# 23005_3.net
KiCad netlist of a schematic drawn in Altium Designer
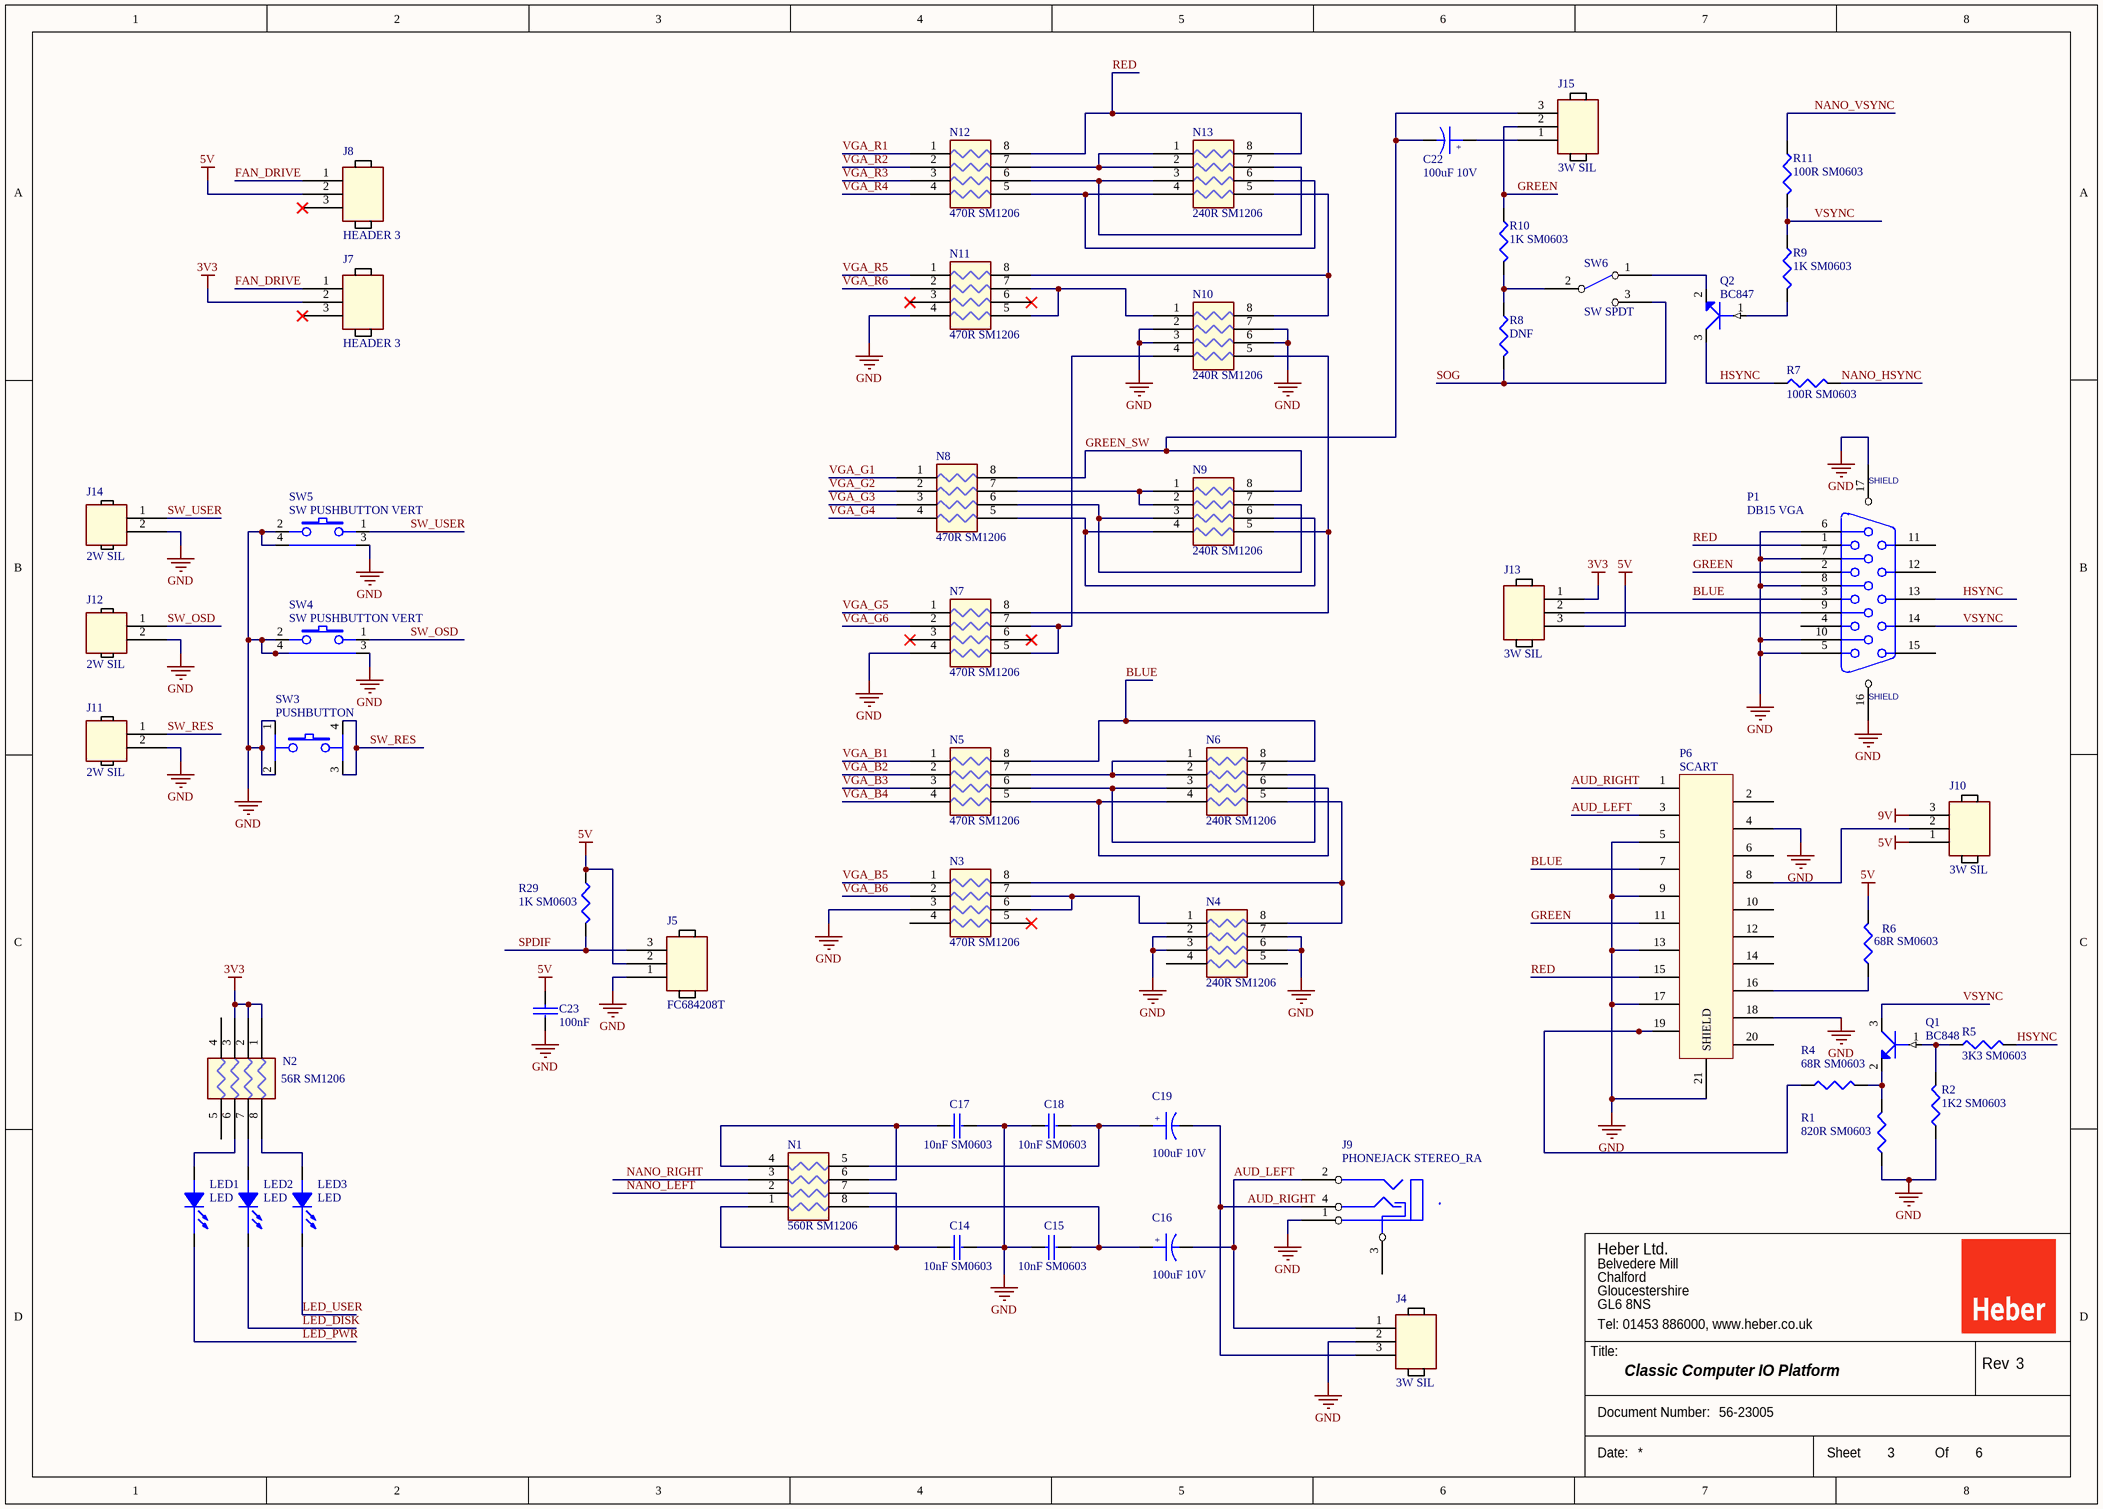
[diagram p0: 23005_3.SchDoc]

(export (version "E")
  (design (tool "Eeschema 10.0.6"))
  (components
    (comp (ref "C14")
      (value "10nF SM0603")
      (footprint "SM0603")
      (libsource (lib "LIBRARY1_Library") (part "C"))
    )
    (comp (ref "C15")
      (value "10nF SM0603")
      (footprint "SM0603")
      (libsource (lib "LIBRARY1_Library") (part "C"))
    )
    (comp (ref "C16")
      (value "100uF 10V")
      (footprint "SM1206")
      (libsource (lib "LIBRARY1_Library") (part "CAP_POL"))
    )
    (comp (ref "C17")
      (value "10nF SM0603")
      (footprint "SM0603")
      (libsource (lib "LIBRARY1_Library") (part "C"))
    )
    (comp (ref "C18")
      (value "10nF SM0603")
      (footprint "SM0603")
      (libsource (lib "LIBRARY1_Library") (part "C"))
    )
    (comp (ref "C19")
      (value "100uF 10V")
      (footprint "SM1206")
      (libsource (lib "LIBRARY1_Library") (part "CAP_POL"))
    )
    (comp (ref "C22")
      (value "100uF 10V")
      (footprint "SM1206")
      (libsource (lib "LIBRARY1_Library") (part "CAP_POL"))
    )
    (comp (ref "C23") (value "100nF") (footprint "SM0603") (libsource (lib "LIBRARY1_Library") (part "C")))
    (comp (ref "J4") (value "3W SIL") (footprint "3WSIL") (libsource (lib "") (part "HEADER 3_2")))
    (comp (ref "J5")
      (value "FC684208T")
      (footprint "FCR684208T")
      (libsource (lib "LIBRARY1_Library") (part "HEADER 3"))
    )
    (comp (ref "J7") (value "HEADER 3") (footprint "3W0.1KK") (libsource (lib "") (part "HEADER 3_2")))
    (comp (ref "J8") (value "HEADER 3") (footprint "3W0.1KK") (libsource (lib "") (part "HEADER 3_2")))
    (comp (ref "J9")
      (value "PHONEJACK STEREO_RA")
      (footprint "JACKSOCKET-STEREO")
      (libsource (lib "LIBRARY1_Library") (part "PHONEJACK STEREO_RA"))
    )
    (comp (ref "J10")
      (value "3W SIL")
      (footprint "3WSIL")
      (libsource (lib "LIBRARY1_Library") (part "HEADER 3"))
    )
    (comp (ref "J11")
      (value "2W SIL")
      (footprint "2WSIL")
      (libsource (lib "LIBRARY1_Library") (part "HEADER 2"))
    )
    (comp (ref "J12")
      (value "2W SIL")
      (footprint "2WSIL")
      (libsource (lib "LIBRARY1_Library") (part "HEADER 2"))
    )
    (comp (ref "J13") (value "3W SIL") (footprint "3WSIL") (libsource (lib "") (part "HEADER 3_1")))
    (comp (ref "J14")
      (value "2W SIL")
      (footprint "2WSIL")
      (libsource (lib "LIBRARY1_Library") (part "HEADER 2"))
    )
    (comp (ref "J15")
      (value "3W SIL")
      (footprint "3WSIL")
      (libsource (lib "LIBRARY1_Library") (part "HEADER 3"))
    )
    (comp (ref "LED1")
      (value "LED")
      (footprint "SM0603LED_1")
      (libsource (lib "LIBRARY1_Library") (part "LED"))
    )
    (comp (ref "LED2")
      (value "LED")
      (footprint "SM0603LED_1")
      (libsource (lib "LIBRARY1_Library") (part "LED"))
    )
    (comp (ref "LED3")
      (value "LED")
      (footprint "SM0603LED_1")
      (libsource (lib "LIBRARY1_Library") (part "LED"))
    )
    (comp (ref "N1")
      (value "560R SM1206")
      (footprint "1206RES4_I2")
      (libsource (lib "LIBRARY1_Library") (part "RESISTOR DIP 4"))
    )
    (comp (ref "N2")
      (value "56R SM1206")
      (footprint "1206RES4_I2")
      (libsource (lib "") (part "RESISTOR DIP 4_2"))
    )
    (comp (ref "N3")
      (value "470R SM1206")
      (footprint "1206RES4_I2")
      (libsource (lib "") (part "RESISTOR DIP 4_1"))
    )
    (comp (ref "N4")
      (value "240R SM1206")
      (footprint "1206RES4_I2")
      (libsource (lib "") (part "RESISTOR DIP 4_1"))
    )
    (comp (ref "N5")
      (value "470R SM1206")
      (footprint "1206RES4_I2")
      (libsource (lib "") (part "RESISTOR DIP 4_1"))
    )
    (comp (ref "N6")
      (value "240R SM1206")
      (footprint "1206RES4_I2")
      (libsource (lib "") (part "RESISTOR DIP 4_1"))
    )
    (comp (ref "N7")
      (value "470R SM1206")
      (footprint "1206RES4_I2")
      (libsource (lib "") (part "RESISTOR DIP 4_1"))
    )
    (comp (ref "N8")
      (value "470R SM1206")
      (footprint "1206RES4_I2")
      (libsource (lib "") (part "RESISTOR DIP 4_1"))
    )
    (comp (ref "N9")
      (value "240R SM1206")
      (footprint "1206RES4_I2")
      (libsource (lib "") (part "RESISTOR DIP 4_1"))
    )
    (comp (ref "N10")
      (value "240R SM1206")
      (footprint "1206RES4_I2")
      (libsource (lib "") (part "RESISTOR DIP 4_1"))
    )
    (comp (ref "N11")
      (value "470R SM1206")
      (footprint "1206RES4_I2")
      (libsource (lib "") (part "RESISTOR DIP 4_1"))
    )
    (comp (ref "N12")
      (value "470R SM1206")
      (footprint "1206RES4_I2")
      (libsource (lib "") (part "RESISTOR DIP 4_1"))
    )
    (comp (ref "N13")
      (value "240R SM1206")
      (footprint "1206RES4_I2")
      (libsource (lib "") (part "RESISTOR DIP 4_1"))
    )
    (comp (ref "P1")
      (value "DB15 VGA")
      (footprint "15WVGASKTRA")
      (libsource (lib "LIBRARY1_Library") (part "CONNECTOR DB15 VGA SHIELDED"))
    )
    (comp (ref "P6")
      (value "SCART")
      (footprint "K-SCART-024")
      (libsource (lib "LIBRARY1_Library") (part "SCART"))
    )
    (comp (ref "Q1")
      (value "BC848")
      (footprint "SOT23")
      (libsource (lib "LIBRARY1_Library") (part "BC846AL_1"))
    )
    (comp (ref "Q2")
      (value "BC847")
      (footprint "SOT23")
      (libsource (lib "LIBRARY1_Library") (part "BC846AL_1"))
    )
    (comp (ref "R1")
      (value "820R SM0603")
      (footprint "SM0603")
      (libsource (lib "LIBRARY1_Library") (part "RES"))
    )
    (comp (ref "R2")
      (value "1K2 SM0603")
      (footprint "SM0603")
      (libsource (lib "LIBRARY1_Library") (part "RES"))
    )
    (comp (ref "R4")
      (value "68R SM0603")
      (footprint "SM0603")
      (libsource (lib "LIBRARY1_Library") (part "RES"))
    )
    (comp (ref "R5")
      (value "3K3 SM0603")
      (footprint "SM0603")
      (libsource (lib "LIBRARY1_Library") (part "RES"))
    )
    (comp (ref "R6")
      (value "68R SM0603")
      (footprint "SM0603")
      (libsource (lib "LIBRARY1_Library") (part "RES"))
    )
    (comp (ref "R7")
      (value "100R SM0603")
      (footprint "SM0603")
      (libsource (lib "LIBRARY1_Library") (part "RES"))
    )
    (comp (ref "R8") (value "DNF") (footprint "SM0603") (libsource (lib "LIBRARY1_Library") (part "RES")))
    (comp (ref "R9")
      (value "1K SM0603")
      (footprint "SM0603")
      (libsource (lib "LIBRARY1_Library") (part "RES"))
    )
    (comp (ref "R10")
      (value "1K SM0603")
      (footprint "SM0603")
      (libsource (lib "LIBRARY1_Library") (part "RES"))
    )
    (comp (ref "R11")
      (value "100R SM0603")
      (footprint "SM0603")
      (libsource (lib "LIBRARY1_Library") (part "RES"))
    )
    (comp (ref "R29")
      (value "1K SM0603")
      (footprint "SM0603")
      (libsource (lib "LIBRARY1_Library") (part "RES"))
    )
    (comp (ref "SW3")
      (value "PUSHBUTTON")
      (footprint "SW_SM_6MM")
      (libsource (lib "LIBRARY1_Library") (part "SW PUSHBUTTON"))
    )
    (comp (ref "SW4")
      (value "SW PUSHBUTTON VERT")
      (footprint "SW_TS6H2A")
      (libsource (lib "LIBRARY1_Library") (part "SW PUSHBUTTON VERT"))
    )
    (comp (ref "SW5")
      (value "SW PUSHBUTTON VERT")
      (footprint "SW_TS6H2A")
      (libsource (lib "LIBRARY1_Library") (part "SW PUSHBUTTON VERT"))
    )
    (comp (ref "SW6")
      (value "SW SPDT")
      (footprint "SW_ITT_OS102011MS2QN1")
      (libsource (lib "LIBRARY1_Library") (part "SW SPDT"))
    )
  )
  (nets
    (net (code "1") (name "/AUD_LEFT") (class "Default")
      (node (ref "C16") (pin "2") (pinfunction "2_2") (pintype "passive"))
      (node (ref "J4") (pin "1") (pinfunction "1_1") (pintype "passive"))
      (node (ref "J9") (pin "2") (pinfunction "2_2") (pintype "passive"))
      (node (ref "P6") (pin "3") (pinfunction "108_3") (pintype "passive"))
    )
    (net (code "2") (name "/AUD_RIGHT") (class "Default")
      (node (ref "C19") (pin "2") (pinfunction "2_2") (pintype "passive"))
      (node (ref "J4") (pin "3") (pinfunction "3_3") (pintype "passive"))
      (node (ref "J9") (pin "4") (pinfunction "4_4") (pintype "passive"))
      (node (ref "P6") (pin "1") (pinfunction "106_1") (pintype "passive"))
    )
    (net (code "3") (name "/BLUE") (class "Default")
      (node (ref "N5") (pin "8") (pinfunction "8_8") (pintype "passive"))
      (node (ref "N6") (pin "8") (pinfunction "8_8") (pintype "passive"))
      (node (ref "P1") (pin "3") (pinfunction "3_3") (pintype "passive"))
      (node (ref "P6") (pin "7") (pinfunction "112_7") (pintype "passive"))
    )
    (net (code "4") (name "/FAN_DRIVE") (class "Default")
      (node (ref "J7") (pin "1") (pinfunction "1_1") (pintype "passive"))
      (node (ref "J8") (pin "1") (pinfunction "1_1") (pintype "passive"))
    )
    (net (code "5") (name "/GREEN") (class "Default")
      (node (ref "J15") (pin "2") (pinfunction "2_2") (pintype "passive"))
      (node (ref "P1") (pin "2") (pinfunction "2_2") (pintype "passive"))
      (node (ref "P6") (pin "11") (pinfunction "112_11") (pintype "passive"))
      (node (ref "R10") (pin "1") (pinfunction "1_1") (pintype "passive"))
    )
    (net (code "6") (name "/GREEN_SW") (class "Default")
      (node (ref "C22") (pin "2") (pinfunction "2_2") (pintype "passive"))
      (node (ref "J15") (pin "3") (pinfunction "3_3") (pintype "passive"))
      (node (ref "N8") (pin "8") (pinfunction "8_8") (pintype "passive"))
      (node (ref "N9") (pin "8") (pinfunction "8_8") (pintype "passive"))
    )
    (net (code "7") (name "/HSYNC") (class "Default")
      (node (ref "P1") (pin "13") (pinfunction "13_13") (pintype "passive"))
      (node (ref "Q2") (pin "3") (pinfunction "C_3") (pintype "passive"))
      (node (ref "R5") (pin "1") (pinfunction "1_1") (pintype "passive"))
      (node (ref "R7") (pin "1") (pinfunction "1_1") (pintype "passive"))
    )
    (net (code "8") (name "/LED_DISK") (class "Default")
      (node (ref "LED2") (pin "2") (pinfunction "CATHODE_2") (pintype "passive"))
    )
    (net (code "9") (name "/LED_PWR") (class "Default")
      (node (ref "LED1") (pin "2") (pinfunction "CATHODE_2") (pintype "passive"))
    )
    (net (code "10") (name "/LED_USER") (class "Default")
      (node (ref "LED3") (pin "2") (pinfunction "CATHODE_2") (pintype "passive"))
    )
    (net (code "11") (name "/NANO_HSYNC") (class "Default")
      (node (ref "R7") (pin "2") (pinfunction "2_2") (pintype "passive"))
    )
    (net (code "12") (name "/NANO_LEFT") (class "Default")
      (node (ref "N1") (pin "2") (pinfunction "2_2") (pintype "passive"))
    )
    (net (code "13") (name "/NANO_RIGHT") (class "Default")
      (node (ref "N1") (pin "3") (pinfunction "3_3") (pintype "passive"))
    )
    (net (code "14") (name "/NANO_VSYNC") (class "Default")
      (node (ref "R11") (pin "1") (pinfunction "1_1") (pintype "passive"))
    )
    (net (code "15") (name "/RED") (class "Default")
      (node (ref "N12") (pin "8") (pinfunction "8_8") (pintype "passive"))
      (node (ref "N13") (pin "8") (pinfunction "8_8") (pintype "passive"))
      (node (ref "P1") (pin "1") (pinfunction "1_1") (pintype "passive"))
      (node (ref "P6") (pin "15") (pinfunction "112_15") (pintype "passive"))
    )
    (net (code "16") (name "/SOG") (class "Default")
      (node (ref "R8") (pin "2") (pinfunction "2_2") (pintype "passive"))
      (node (ref "SW6") (pin "3") (pinfunction "NO_3") (pintype "passive"))
    )
    (net (code "17") (name "/SPDIF") (class "Default")
      (node (ref "J5") (pin "3") (pinfunction "3_3") (pintype "passive"))
      (node (ref "R29") (pin "2") (pinfunction "2_2") (pintype "passive"))
    )
    (net (code "18") (name "/SW_OSD") (class "Default")
      (node (ref "J12") (pin "1") (pinfunction "1_1") (pintype "passive"))
      (node (ref "SW4") (pin "1") (pinfunction "3_1") (pintype "passive"))
    )
    (net (code "19") (name "/SW_RES") (class "Default")
      (node (ref "J11") (pin "1") (pinfunction "1_1") (pintype "passive"))
      (node (ref "SW3") (pin "3") (pinfunction "2_3") (pintype "passive"))
      (node (ref "SW3") (pin "4") (pinfunction "4_4") (pintype "passive"))
    )
    (net (code "20") (name "/SW_USER") (class "Default")
      (node (ref "J14") (pin "1") (pinfunction "1_1") (pintype "passive"))
      (node (ref "SW5") (pin "1") (pinfunction "3_1") (pintype "passive"))
    )
    (net (code "21") (name "/VGA_B1") (class "Default")
      (node (ref "N5") (pin "1") (pinfunction "1_1") (pintype "passive"))
    )
    (net (code "22") (name "/VGA_B2") (class "Default")
      (node (ref "N5") (pin "2") (pinfunction "2_2") (pintype "passive"))
    )
    (net (code "23") (name "/VGA_B3") (class "Default")
      (node (ref "N5") (pin "3") (pinfunction "3_3") (pintype "passive"))
    )
    (net (code "24") (name "/VGA_B4") (class "Default")
      (node (ref "N5") (pin "4") (pinfunction "4_4") (pintype "passive"))
    )
    (net (code "25") (name "/VGA_B5") (class "Default")
      (node (ref "N3") (pin "1") (pinfunction "1_1") (pintype "passive"))
    )
    (net (code "26") (name "/VGA_B6") (class "Default")
      (node (ref "N3") (pin "2") (pinfunction "2_2") (pintype "passive"))
    )
    (net (code "27") (name "/VGA_G1") (class "Default")
      (node (ref "N8") (pin "1") (pinfunction "1_1") (pintype "passive"))
    )
    (net (code "28") (name "/VGA_G2") (class "Default")
      (node (ref "N8") (pin "2") (pinfunction "2_2") (pintype "passive"))
    )
    (net (code "29") (name "/VGA_G3") (class "Default")
      (node (ref "N8") (pin "3") (pinfunction "3_3") (pintype "passive"))
    )
    (net (code "30") (name "/VGA_G4") (class "Default")
      (node (ref "N8") (pin "4") (pinfunction "4_4") (pintype "passive"))
    )
    (net (code "31") (name "/VGA_G5") (class "Default")
      (node (ref "N7") (pin "1") (pinfunction "1_1") (pintype "passive"))
    )
    (net (code "32") (name "/VGA_G6") (class "Default")
      (node (ref "N7") (pin "2") (pinfunction "2_2") (pintype "passive"))
    )
    (net (code "33") (name "/VGA_R1") (class "Default")
      (node (ref "N12") (pin "1") (pinfunction "1_1") (pintype "passive"))
    )
    (net (code "34") (name "/VGA_R2") (class "Default")
      (node (ref "N12") (pin "2") (pinfunction "2_2") (pintype "passive"))
    )
    (net (code "35") (name "/VGA_R3") (class "Default")
      (node (ref "N12") (pin "3") (pinfunction "3_3") (pintype "passive"))
    )
    (net (code "36") (name "/VGA_R4") (class "Default")
      (node (ref "N12") (pin "4") (pinfunction "4_4") (pintype "passive"))
    )
    (net (code "37") (name "/VGA_R5") (class "Default")
      (node (ref "N11") (pin "1") (pinfunction "1_1") (pintype "passive"))
    )
    (net (code "38") (name "/VGA_R6") (class "Default")
      (node (ref "N11") (pin "2") (pinfunction "2_2") (pintype "passive"))
    )
    (net (code "39") (name "/VSYNC") (class "Default")
      (node (ref "P1") (pin "14") (pinfunction "14_14") (pintype "passive"))
      (node (ref "Q1") (pin "3") (pinfunction "C_3") (pintype "passive"))
      (node (ref "R11") (pin "2") (pinfunction "2_2") (pintype "passive"))
      (node (ref "R9") (pin "1") (pinfunction "1_1") (pintype "passive"))
    )
    (net (code "40") (name "3V3") (class "Default")
      (node (ref "J13") (pin "1") (pinfunction "1_1") (pintype "passive"))
      (node (ref "J7") (pin "2") (pinfunction "2_2") (pintype "passive"))
      (node (ref "N2") (pin "1") (pinfunction "1_1") (pintype "passive"))
      (node (ref "N2") (pin "2") (pinfunction "2_2") (pintype "passive"))
      (node (ref "N2") (pin "3") (pinfunction "3_3") (pintype "passive"))
    )
    (net (code "41") (name "5V") (class "Default")
      (node (ref "C23") (pin "1") (pinfunction "1_1") (pintype "passive"))
      (node (ref "J10") (pin "1") (pinfunction "1_1") (pintype "passive"))
      (node (ref "J13") (pin "3") (pinfunction "3_3") (pintype "passive"))
      (node (ref "J5") (pin "2") (pinfunction "2_2") (pintype "passive"))
      (node (ref "J8") (pin "2") (pinfunction "2_2") (pintype "passive"))
      (node (ref "R29") (pin "1") (pinfunction "1_1") (pintype "passive"))
      (node (ref "R6") (pin "2") (pinfunction "2_2") (pintype "passive"))
    )
    (net (code "42") (name "9V") (class "Default")
      (node (ref "J10") (pin "3") (pinfunction "3_3") (pintype "passive"))
    )
    (net (code "43") (name "GND") (class "Default")
      (node (ref "C14") (pin "2") (pinfunction "2_2") (pintype "passive"))
      (node (ref "C15") (pin "1") (pinfunction "1_1") (pintype "passive"))
      (node (ref "C17") (pin "2") (pinfunction "2_2") (pintype "passive"))
      (node (ref "C18") (pin "1") (pinfunction "1_1") (pintype "passive"))
      (node (ref "C23") (pin "2") (pinfunction "2_2") (pintype "passive"))
      (node (ref "J11") (pin "2") (pinfunction "2_2") (pintype "passive"))
      (node (ref "J12") (pin "2") (pinfunction "2_2") (pintype "passive"))
      (node (ref "J14") (pin "2") (pinfunction "2_2") (pintype "passive"))
      (node (ref "J4") (pin "2") (pinfunction "2_2") (pintype "passive"))
      (node (ref "J5") (pin "1") (pinfunction "1_1") (pintype "passive"))
      (node (ref "J9") (pin "1") (pinfunction "1_1") (pintype "passive"))
      (node (ref "N10") (pin "2") (pinfunction "2_2") (pintype "passive"))
      (node (ref "N10") (pin "3") (pinfunction "3_3") (pintype "passive"))
      (node (ref "N10") (pin "6") (pinfunction "6_6") (pintype "passive"))
      (node (ref "N10") (pin "7") (pinfunction "7_7") (pintype "passive"))
      (node (ref "N11") (pin "4") (pinfunction "4_4") (pintype "passive"))
      (node (ref "N3") (pin "3") (pinfunction "3_3") (pintype "passive"))
      (node (ref "N4") (pin "2") (pinfunction "2_2") (pintype "passive"))
      (node (ref "N4") (pin "3") (pinfunction "3_3") (pintype "passive"))
      (node (ref "N4") (pin "6") (pinfunction "6_6") (pintype "passive"))
      (node (ref "N4") (pin "7") (pinfunction "7_7") (pintype "passive"))
      (node (ref "N7") (pin "4") (pinfunction "4_4") (pintype "passive"))
      (node (ref "P1") (pin "10") (pinfunction "10_10") (pintype "passive"))
      (node (ref "P1") (pin "16") (pinfunction "16_16") (pintype "passive"))
      (node (ref "P1") (pin "17") (pinfunction "17_17") (pintype "passive"))
      (node (ref "P1") (pin "5") (pinfunction "5_5") (pintype "passive"))
      (node (ref "P1") (pin "6") (pinfunction "6_6") (pintype "passive"))
      (node (ref "P1") (pin "7") (pinfunction "7_7") (pintype "passive"))
      (node (ref "P1") (pin "8") (pinfunction "8_8") (pintype "passive"))
      (node (ref "P6") (pin "13") (pinfunction "112_13") (pintype "passive"))
      (node (ref "P6") (pin "17") (pinfunction "112_17") (pintype "passive"))
      (node (ref "P6") (pin "18") (pinfunction "112_18") (pintype "passive"))
      (node (ref "P6") (pin "21") (pinfunction "SHIELD_21") (pintype "passive"))
      (node (ref "P6") (pin "4") (pinfunction "109_4") (pintype "passive"))
      (node (ref "P6") (pin "5") (pinfunction "110_5") (pintype "passive"))
      (node (ref "P6") (pin "9") (pinfunction "112_9") (pintype "passive"))
      (node (ref "R1") (pin "2") (pinfunction "2_2") (pintype "passive"))
      (node (ref "R2") (pin "2") (pinfunction "2_2") (pintype "passive"))
      (node (ref "SW3") (pin "1") (pinfunction "3_1") (pintype "passive"))
      (node (ref "SW3") (pin "2") (pinfunction "1_2") (pintype "passive"))
      (node (ref "SW4") (pin "2") (pinfunction "1_2") (pintype "passive"))
      (node (ref "SW4") (pin "3") (pinfunction "2_3") (pintype "passive"))
      (node (ref "SW4") (pin "4") (pinfunction "4_4") (pintype "passive"))
      (node (ref "SW5") (pin "2") (pinfunction "1_2") (pintype "passive"))
      (node (ref "SW5") (pin "3") (pinfunction "2_3") (pintype "passive"))
      (node (ref "SW5") (pin "4") (pinfunction "4_4") (pintype "passive"))
    )
    (net (code "44") (name "Net-(C14-Pad1)") (class "Default")
      (node (ref "C14") (pin "1") (pinfunction "1_1") (pintype "passive"))
      (node (ref "N1") (pin "1") (pinfunction "1_1") (pintype "passive"))
      (node (ref "N1") (pin "7") (pinfunction "7_7") (pintype "passive"))
    )
    (net (code "45") (name "Net-(C15-Pad2)") (class "Default")
      (node (ref "C15") (pin "2") (pinfunction "2_2") (pintype "passive"))
      (node (ref "C16") (pin "1") (pinfunction "1_1") (pintype "passive"))
      (node (ref "N1") (pin "8") (pinfunction "8_8") (pintype "passive"))
    )
    (net (code "46") (name "Net-(C17-Pad1)") (class "Default")
      (node (ref "C17") (pin "1") (pinfunction "1_1") (pintype "passive"))
      (node (ref "N1") (pin "4") (pinfunction "4_4") (pintype "passive"))
      (node (ref "N1") (pin "6") (pinfunction "6_6") (pintype "passive"))
    )
    (net (code "47") (name "Net-(C18-Pad2)") (class "Default")
      (node (ref "C18") (pin "2") (pinfunction "2_2") (pintype "passive"))
      (node (ref "C19") (pin "1") (pinfunction "1_1") (pintype "passive"))
      (node (ref "N1") (pin "5") (pinfunction "5_5") (pintype "passive"))
    )
    (net (code "48") (name "Net-(C22-Pad1)") (class "Default")
      (node (ref "C22") (pin "1") (pinfunction "1_1") (pintype "passive"))
      (node (ref "J15") (pin "1") (pinfunction "1_1") (pintype "passive"))
    )
    (net (code "49") (name "Net-(J10-Pad2)") (class "Default")
      (node (ref "J10") (pin "2") (pinfunction "2_2") (pintype "passive"))
      (node (ref "P6") (pin "8") (pinfunction "112_8") (pintype "passive"))
    )
    (net (code "50") (name "Net-(J13-Pad2)") (class "Default")
      (node (ref "J13") (pin "2") (pinfunction "2_2") (pintype "passive"))
      (node (ref "P1") (pin "9") (pinfunction "9_9") (pintype "passive"))
    )
    (net (code "51") (name "Net-(LED1-ANODE)") (class "Default")
      (node (ref "LED1") (pin "1") (pinfunction "ANODE_1") (pintype "passive"))
      (node (ref "N2") (pin "6") (pinfunction "6_6") (pintype "passive"))
    )
    (net (code "52") (name "Net-(LED2-ANODE)") (class "Default")
      (node (ref "LED2") (pin "1") (pinfunction "ANODE_1") (pintype "passive"))
      (node (ref "N2") (pin "7") (pinfunction "7_7") (pintype "passive"))
    )
    (net (code "53") (name "Net-(LED3-ANODE)") (class "Default")
      (node (ref "LED3") (pin "1") (pinfunction "ANODE_1") (pintype "passive"))
      (node (ref "N2") (pin "8") (pinfunction "8_8") (pintype "passive"))
    )
    (net (code "54") (name "Net-(N3-Pad6)") (class "Default")
      (node (ref "N3") (pin "6") (pinfunction "6_6") (pintype "passive"))
      (node (ref "N3") (pin "7") (pinfunction "7_7") (pintype "passive"))
      (node (ref "N4") (pin "1") (pinfunction "1_1") (pintype "passive"))
    )
    (net (code "55") (name "Net-(N3-Pad8)") (class "Default")
      (node (ref "N3") (pin "8") (pinfunction "8_8") (pintype "passive"))
      (node (ref "N4") (pin "8") (pinfunction "8_8") (pintype "passive"))
      (node (ref "N6") (pin "5") (pinfunction "5_5") (pintype "passive"))
    )
    (net (code "56") (name "Net-(N5-Pad5)") (class "Default")
      (node (ref "N5") (pin "5") (pinfunction "5_5") (pintype "passive"))
      (node (ref "N6") (pin "4") (pinfunction "4_4") (pintype "passive"))
      (node (ref "N6") (pin "6") (pinfunction "6_6") (pintype "passive"))
    )
    (net (code "57") (name "Net-(N5-Pad6)") (class "Default")
      (node (ref "N5") (pin "6") (pinfunction "6_6") (pintype "passive"))
      (node (ref "N6") (pin "3") (pinfunction "3_3") (pintype "passive"))
      (node (ref "N6") (pin "7") (pinfunction "7_7") (pintype "passive"))
    )
    (net (code "58") (name "Net-(N5-Pad7)") (class "Default")
      (node (ref "N5") (pin "7") (pinfunction "7_7") (pintype "passive"))
      (node (ref "N6") (pin "1") (pinfunction "1_1") (pintype "passive"))
      (node (ref "N6") (pin "2") (pinfunction "2_2") (pintype "passive"))
    )
    (net (code "59") (name "Net-(N8-Pad5)") (class "Default")
      (node (ref "N8") (pin "5") (pinfunction "5_5") (pintype "passive"))
      (node (ref "N9") (pin "4") (pinfunction "4_4") (pintype "passive"))
      (node (ref "N9") (pin "6") (pinfunction "6_6") (pintype "passive"))
    )
    (net (code "60") (name "Net-(N8-Pad6)") (class "Default")
      (node (ref "N8") (pin "6") (pinfunction "6_6") (pintype "passive"))
      (node (ref "N9") (pin "3") (pinfunction "3_3") (pintype "passive"))
      (node (ref "N9") (pin "7") (pinfunction "7_7") (pintype "passive"))
    )
    (net (code "61") (name "Net-(N8-Pad7)") (class "Default")
      (node (ref "N8") (pin "7") (pinfunction "7_7") (pintype "passive"))
      (node (ref "N9") (pin "1") (pinfunction "1_1") (pintype "passive"))
      (node (ref "N9") (pin "2") (pinfunction "2_2") (pintype "passive"))
    )
    (net (code "62") (name "Net-(N10-Pad1)") (class "Default")
      (node (ref "N10") (pin "1") (pinfunction "1_1") (pintype "passive"))
      (node (ref "N11") (pin "5") (pinfunction "5_5") (pintype "passive"))
      (node (ref "N11") (pin "7") (pinfunction "7_7") (pintype "passive"))
    )
    (net (code "63") (name "Net-(N10-Pad4)") (class "Default")
      (node (ref "N10") (pin "4") (pinfunction "4_4") (pintype "passive"))
      (node (ref "N7") (pin "5") (pinfunction "5_5") (pintype "passive"))
      (node (ref "N7") (pin "7") (pinfunction "7_7") (pintype "passive"))
    )
    (net (code "64") (name "Net-(N10-Pad5)") (class "Default")
      (node (ref "N10") (pin "5") (pinfunction "5_5") (pintype "passive"))
      (node (ref "N7") (pin "8") (pinfunction "8_8") (pintype "passive"))
      (node (ref "N9") (pin "5") (pinfunction "5_5") (pintype "passive"))
    )
    (net (code "65") (name "Net-(N10-Pad8)") (class "Default")
      (node (ref "N10") (pin "8") (pinfunction "8_8") (pintype "passive"))
      (node (ref "N11") (pin "8") (pinfunction "8_8") (pintype "passive"))
      (node (ref "N13") (pin "5") (pinfunction "5_5") (pintype "passive"))
    )
    (net (code "66") (name "Net-(N12-Pad5)") (class "Default")
      (node (ref "N12") (pin "5") (pinfunction "5_5") (pintype "passive"))
      (node (ref "N13") (pin "4") (pinfunction "4_4") (pintype "passive"))
      (node (ref "N13") (pin "6") (pinfunction "6_6") (pintype "passive"))
    )
    (net (code "67") (name "Net-(N12-Pad6)") (class "Default")
      (node (ref "N12") (pin "6") (pinfunction "6_6") (pintype "passive"))
      (node (ref "N13") (pin "3") (pinfunction "3_3") (pintype "passive"))
      (node (ref "N13") (pin "7") (pinfunction "7_7") (pintype "passive"))
    )
    (net (code "68") (name "Net-(N12-Pad7)") (class "Default")
      (node (ref "N12") (pin "7") (pinfunction "7_7") (pintype "passive"))
      (node (ref "N13") (pin "1") (pinfunction "1_1") (pintype "passive"))
      (node (ref "N13") (pin "2") (pinfunction "2_2") (pintype "passive"))
    )
    (net (code "69") (name "Net-(P6-112-Pad16)") (class "Default")
      (node (ref "P6") (pin "16") (pinfunction "112_16") (pintype "passive"))
      (node (ref "R6") (pin "1") (pinfunction "1_1") (pintype "passive"))
    )
    (net (code "70") (name "Net-(P6-112-Pad19)") (class "Default")
      (node (ref "P6") (pin "19") (pinfunction "112_19") (pintype "passive"))
      (node (ref "R4") (pin "2") (pinfunction "2_2") (pintype "passive"))
    )
    (net (code "71") (name "Net-(Q1-B)") (class "Default")
      (node (ref "Q1") (pin "1") (pinfunction "B_1") (pintype "input"))
      (node (ref "R2") (pin "1") (pinfunction "1_1") (pintype "passive"))
      (node (ref "R5") (pin "2") (pinfunction "2_2") (pintype "passive"))
    )
    (net (code "72") (name "Net-(Q1-E)") (class "Default")
      (node (ref "Q1") (pin "2") (pinfunction "E_2") (pintype "passive"))
      (node (ref "R1") (pin "1") (pinfunction "1_1") (pintype "passive"))
      (node (ref "R4") (pin "1") (pinfunction "1_1") (pintype "passive"))
    )
    (net (code "73") (name "Net-(Q2-B)") (class "Default")
      (node (ref "Q2") (pin "1") (pinfunction "B_1") (pintype "input"))
      (node (ref "R9") (pin "2") (pinfunction "2_2") (pintype "passive"))
    )
    (net (code "74") (name "Net-(Q2-E)") (class "Default")
      (node (ref "Q2") (pin "2") (pinfunction "E_2") (pintype "passive"))
      (node (ref "SW6") (pin "1") (pinfunction "NC_1") (pintype "passive"))
    )
    (net (code "75") (name "Net-(SW6-COMMON)") (class "Default")
      (node (ref "R10") (pin "2") (pinfunction "2_2") (pintype "passive"))
      (node (ref "R8") (pin "1") (pinfunction "1_1") (pintype "passive"))
      (node (ref "SW6") (pin "2") (pinfunction "COMMON_2") (pintype "passive"))
    )
    (net (code "76") (name "unconnected-(J7-Pad3)") (class "Default")
      (node (ref "J7") (pin "3") (pinfunction "3_3") (pintype "passive+no_connect"))
    )
    (net (code "77") (name "unconnected-(J8-Pad3)") (class "Default")
      (node (ref "J8") (pin "3") (pinfunction "3_3") (pintype "passive+no_connect"))
    )
    (net (code "78") (name "unconnected-(J9-Pad3)") (class "Default")
      (node (ref "J9") (pin "3") (pinfunction "3_3") (pintype "passive"))
    )
    (net (code "79") (name "unconnected-(N2-Pad4)") (class "Default")
      (node (ref "N2") (pin "4") (pinfunction "4_4") (pintype "passive"))
    )
    (net (code "80") (name "unconnected-(N2-Pad5)") (class "Default")
      (node (ref "N2") (pin "5") (pinfunction "5_5") (pintype "passive"))
    )
    (net (code "81") (name "unconnected-(N3-Pad4)") (class "Default")
      (node (ref "N3") (pin "4") (pinfunction "4_4") (pintype "passive"))
    )
    (net (code "82") (name "unconnected-(N3-Pad5)") (class "Default")
      (node (ref "N3") (pin "5") (pinfunction "5_5") (pintype "passive+no_connect"))
    )
    (net (code "83") (name "unconnected-(N4-Pad4)") (class "Default")
      (node (ref "N4") (pin "4") (pinfunction "4_4") (pintype "passive"))
    )
    (net (code "84") (name "unconnected-(N4-Pad5)") (class "Default")
      (node (ref "N4") (pin "5") (pinfunction "5_5") (pintype "passive"))
    )
    (net (code "85") (name "unconnected-(N7-Pad3)") (class "Default")
      (node (ref "N7") (pin "3") (pinfunction "3_3") (pintype "passive+no_connect"))
    )
    (net (code "86") (name "unconnected-(N7-Pad6)") (class "Default")
      (node (ref "N7") (pin "6") (pinfunction "6_6") (pintype "passive+no_connect"))
    )
    (net (code "87") (name "unconnected-(N11-Pad3)") (class "Default")
      (node (ref "N11") (pin "3") (pinfunction "3_3") (pintype "passive+no_connect"))
    )
    (net (code "88") (name "unconnected-(N11-Pad6)") (class "Default")
      (node (ref "N11") (pin "6") (pinfunction "6_6") (pintype "passive+no_connect"))
    )
    (net (code "89") (name "unconnected-(P1-Pad4)") (class "Default")
      (node (ref "P1") (pin "4") (pinfunction "4_4") (pintype "passive"))
    )
    (net (code "90") (name "unconnected-(P1-Pad11)") (class "Default")
      (node (ref "P1") (pin "11") (pinfunction "11_11") (pintype "passive"))
    )
    (net (code "91") (name "unconnected-(P1-Pad12)") (class "Default")
      (node (ref "P1") (pin "12") (pinfunction "12_12") (pintype "passive"))
    )
    (net (code "92") (name "unconnected-(P1-Pad15)") (class "Default")
      (node (ref "P1") (pin "15") (pinfunction "15_15") (pintype "passive"))
    )
    (net (code "93") (name "unconnected-(P6-107-Pad2)") (class "Default")
      (node (ref "P6") (pin "2") (pinfunction "107_2") (pintype "passive"))
    )
    (net (code "94") (name "unconnected-(P6-111-Pad6)") (class "Default")
      (node (ref "P6") (pin "6") (pinfunction "111_6") (pintype "passive"))
    )
    (net (code "95") (name "unconnected-(P6-112-Pad10)") (class "Default")
      (node (ref "P6") (pin "10") (pinfunction "112_10") (pintype "passive"))
    )
    (net (code "96") (name "unconnected-(P6-112-Pad12)") (class "Default")
      (node (ref "P6") (pin "12") (pinfunction "112_12") (pintype "passive"))
    )
    (net (code "97") (name "unconnected-(P6-112-Pad14)") (class "Default")
      (node (ref "P6") (pin "14") (pinfunction "112_14") (pintype "passive"))
    )
    (net (code "98") (name "unconnected-(P6-112-Pad20)") (class "Default")
      (node (ref "P6") (pin "20") (pinfunction "112_20") (pintype "passive"))
    )
  )
)
